# rotencoder.net
KiCad netlist of a schematic drawn in EAGLE
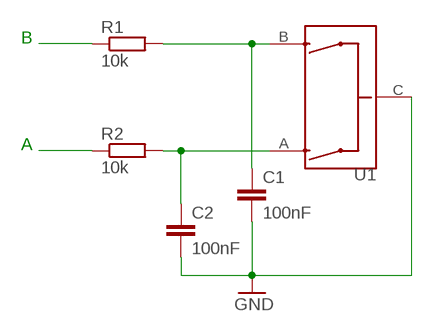
[diagram p0: schematic, sheet 1]

(export (version "E")
  (design (tool "Eeschema 10.0.6"))
  (components
    (comp (ref "C1")
      (value "100nF")
      (footprint "eagle-import:C025-040X050")
      (libsource (lib "eagle-import") (part "C-EU025-040X050"))
    )
    (comp (ref "C2")
      (value "100nF")
      (footprint "eagle-import:C025-040X050")
      (libsource (lib "eagle-import") (part "C-EU025-040X050"))
    )
    (comp (ref "R1")
      (value "10k")
      (footprint "eagle-import:0309_12")
      (libsource (lib "eagle-import") (part "R-EU_0309/12"))
    )
    (comp (ref "R2")
      (value "10k")
      (footprint "eagle-import:0309_12")
      (libsource (lib "eagle-import") (part "R-EU_0309/12"))
    )
    (comp (ref "U1")
      (value "ENCODER-QUADRATURE")
      (footprint "eagle-import:ENCODER-16MM-QUAD")
      (libsource (lib "eagle-import") (part "ENCODER-QUADRATURE"))
    )
  )
  (nets
    (net (code "1") (name "GND") (class "Default")
      (node (ref "C1") (pin "2") (pinfunction "2_2") (pintype "passive"))
      (node (ref "C2") (pin "2") (pinfunction "2_2") (pintype "passive"))
      (node (ref "U1") (pin "C") (pinfunction "C_C") (pintype "bidirectional"))
    )
    (net (code "2") (name "Net-(C1-Pad1)") (class "Default")
      (node (ref "C1") (pin "1") (pinfunction "1_1") (pintype "passive"))
      (node (ref "R1") (pin "2") (pinfunction "2_2") (pintype "passive"))
      (node (ref "U1") (pin "B") (pinfunction "B_B") (pintype "bidirectional"))
    )
    (net (code "3") (name "Net-(C2-Pad1)") (class "Default")
      (node (ref "C2") (pin "1") (pinfunction "1_1") (pintype "passive"))
      (node (ref "R2") (pin "2") (pinfunction "2_2") (pintype "passive"))
      (node (ref "U1") (pin "A") (pinfunction "A_A") (pintype "bidirectional"))
    )
    (net (code "4") (name "unconnected-(R1-Pad1)") (class "Default")
      (node (ref "R1") (pin "1") (pinfunction "1_1") (pintype "passive"))
    )
    (net (code "5") (name "unconnected-(R2-Pad1)") (class "Default")
      (node (ref "R2") (pin "1") (pinfunction "1_1") (pintype "passive"))
    )
  )
)
